# VS_Project_HW01.net
KiCad netlist of a schematic drawn in EasyEDA Pro
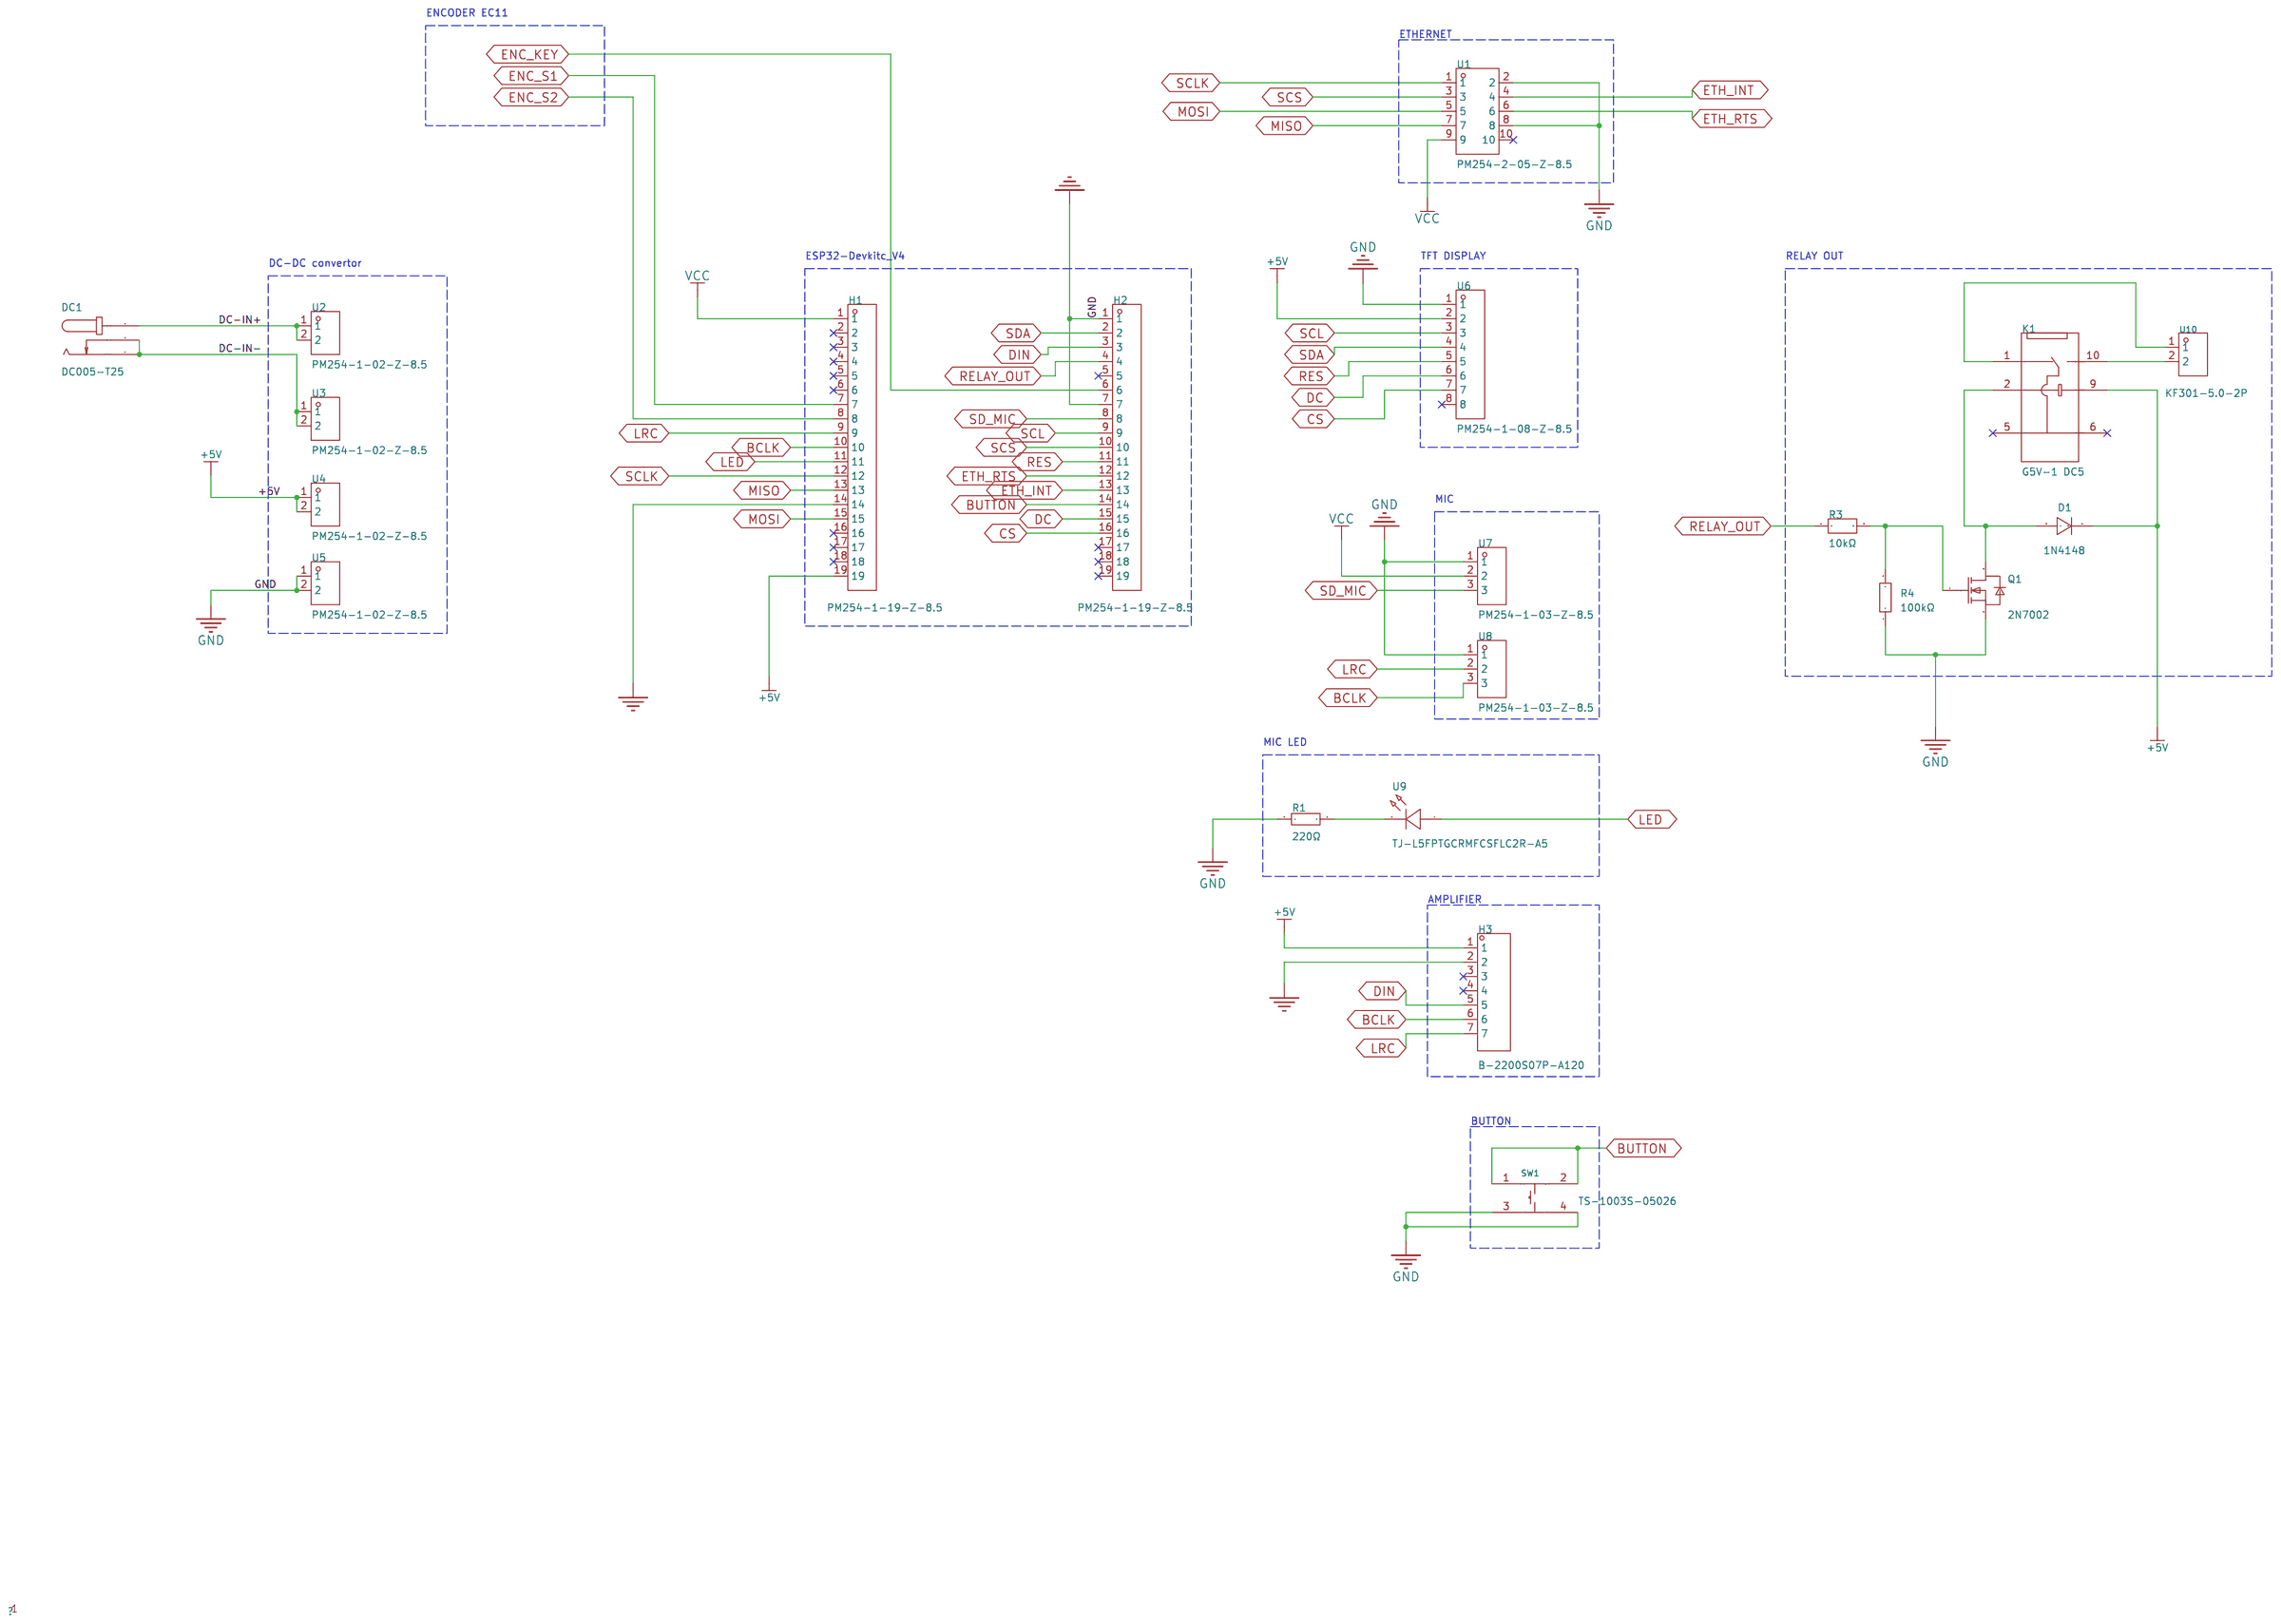
[diagram p0: schematic sheet]

(export (version "E")
  (design (tool "Eeschema 10.0.6"))
  (components
    (comp (ref "D1")
      (value "1N4148")
      (footprint "easyedapro:DO-35_BD2.0-L4.2-P8.20-D0.5-RD")
      (fields (field (name "Manufacturer") "GOOD-ARK(固锝)"))
      (libsource (lib "easyedapro") (part "1N4148_C406389"))
    )
    (comp (ref "DC1")
      (value "DC005-T25")
      (footprint "easyedapro:DC-IN-TH_DC-005-20A-1")
      (fields (field (name "Manufacturer") "SOFNG(硕方)"))
      (libsource (lib "easyedapro") (part "DC005-2.5MM"))
    )
    (comp (ref "H1")
      (value "PM254-1-19-Z-8.5")
      (footprint "easyedapro:HDR-TH_19P-P2.54-V-F")
      (fields (field (name "Manufacturer") "HCTL(华灿天禄)"))
      (libsource (lib "easyedapro") (part "HDR-F_2.54_1x19P"))
    )
    (comp (ref "H2")
      (value "PM254-1-19-Z-8.5")
      (footprint "easyedapro:HDR-TH_19P-P2.54-V-F")
      (fields (field (name "Manufacturer") "HCTL(华灿天禄)"))
      (libsource (lib "easyedapro") (part "HDR-F_2.54_1x19P"))
    )
    (comp (ref "H3")
      (value "B-2200S07P-A120")
      (footprint "easyedapro:HDR-TH_7P-P2.54-V-F")
      (fields (field (name "Manufacturer") "Ckmtw(灿科盟)"))
      (libsource (lib "easyedapro") (part "220S-1*7P H=8.5MM Ytype Gold-plated"))
    )
    (comp (ref "K1")
      (value "G5V-1 DC5")
      (footprint "easyedapro:RELAY-TH_G5V-1")
      (fields (field (name "Manufacturer") "OMRON(欧姆龙)"))
      (libsource (lib "easyedapro") (part "G5V-1-DC3"))
    )
    (comp (ref "Q1")
      (value "2N7002")
      (footprint "easyedapro:SOT-23-3_L2.9-W1.3-P1.90-LS2.4-BR")
      (fields (field (name "Manufacturer") "YFW(佑风微)"))
      (libsource (lib "easyedapro") (part "2N7002_C42395051"))
    )
    (comp (ref "R1")
      (value "220Ω")
      (footprint "easyedapro:R0603")
      (fields (field (name "Manufacturer Part") "RC0603FR-07220RL") (field (name "Manufacturer") "YAGEO(国巨)"))
      (libsource (lib "easyedapro") (part "Res"))
    )
    (comp (ref "R3")
      (value "10kΩ")
      (footprint "easyedapro:R0603")
      (fields (field (name "Manufacturer Part") "RC0603JR-0710KL") (field (name "Manufacturer") "YAGEO(国巨)"))
      (libsource (lib "easyedapro") (part "SCR0603J10K"))
    )
    (comp (ref "R4")
      (value "100kΩ")
      (footprint "easyedapro:R0603")
      (fields (field (name "Manufacturer Part") "RC0603FR-07100KL") (field (name "Manufacturer") "YAGEO(国巨)"))
      (libsource (lib "easyedapro") (part "Res"))
    )
    (comp (ref "SW1")
      (value "TS-1003S-05026")
      (footprint "easyedapro:KEY-SMD_4P-L12.0-W12.0-P5.00-LS15.2")
      (fields (field (name "Manufacturer") "XUNPU(讯普)"))
      (libsource (lib "easyedapro") (part "TS-1003S-05026"))
    )
    (comp (ref "U1")
      (value "PM254-2-05-Z-8.5")
      (footprint "easyedapro:HDR-TH_10P-P2.54-V-F-R2-C5-S2.54")
      (fields (field (name "Manufacturer") "HCTL(华灿天禄)"))
      (libsource (lib "easyedapro") (part "PM254-2-05-Z-8.5"))
    )
    (comp (ref "U2")
      (value "PM254-1-02-Z-8.5")
      (footprint "easyedapro:HDR-TH_2P-P2.54-V-F-3")
      (fields (field (name "Manufacturer") "HCTL(华灿天禄)"))
      (libsource (lib "easyedapro") (part "PM254-1-02-Z-8.5_C3012024"))
    )
    (comp (ref "U3")
      (value "PM254-1-02-Z-8.5")
      (footprint "easyedapro:HDR-TH_2P-P2.54-V-F-3")
      (fields (field (name "Manufacturer") "HCTL(华灿天禄)"))
      (libsource (lib "easyedapro") (part "PM254-1-02-Z-8.5_C3012024"))
    )
    (comp (ref "U4")
      (value "PM254-1-02-Z-8.5")
      (footprint "easyedapro:HDR-TH_2P-P2.54-V-F-3")
      (fields (field (name "Manufacturer") "HCTL(华灿天禄)"))
      (libsource (lib "easyedapro") (part "PM254-1-02-Z-8.5_C3012024"))
    )
    (comp (ref "U5")
      (value "PM254-1-02-Z-8.5")
      (footprint "easyedapro:HDR-TH_2P-P2.54-V-F-3")
      (fields (field (name "Manufacturer") "HCTL(华灿天禄)"))
      (libsource (lib "easyedapro") (part "PM254-1-02-Z-8.5_C3012024"))
    )
    (comp (ref "U6")
      (value "PM254-1-08-Z-8.5")
      (footprint "easyedapro:HDR-TH_8P-P2.54-V-F")
      (fields (field (name "Manufacturer") "HCTL(华灿天禄)"))
      (libsource (lib "easyedapro") (part "PM254-1-08-Z-8.5"))
    )
    (comp (ref "U7")
      (value "PM254-1-03-Z-8.5")
      (footprint "easyedapro:HDR-TH_3P-P2.54-V-F")
      (fields (field (name "Manufacturer") "HCTL(华灿天禄)"))
      (libsource (lib "easyedapro") (part "PM254-1-03-Z-8.5"))
    )
    (comp (ref "U8")
      (value "PM254-1-03-Z-8.5")
      (footprint "easyedapro:HDR-TH_3P-P2.54-V-F")
      (fields (field (name "Manufacturer") "HCTL(华灿天禄)"))
      (libsource (lib "easyedapro") (part "PM254-1-03-Z-8.5"))
    )
    (comp (ref "U9")
      (value "TJ-L5FPTGCRMFCSFLC2R-A5")
      (footprint "easyedapro:LED-TH_BD5.8-P2.54-FD")
      (description "Lamp Holder Type:5mm圆柱形灯头 Emitted Color:Red Lens Color:雾状红透镜")
      (fields (field (name "Manufacturer") "TOGIALED(统佳)"))
      (libsource (lib "easyedapro") (part "TJ-L5FPTGCRMFCSFLC2R-A5"))
    )
    (comp (ref "U10")
      (value "KF301-5.0-2P")
      (footprint "easyedapro:CONN-TH_P5.00_KF301-5.0-2P")
      (fields (field (name "Manufacturer") "KEFA(科发)"))
      (libsource (lib "easyedapro") (part "KF301-5.0-2P"))
    )
  )
  (nets
    (net (code "1") (name "+5V") (class "Default")
      (node (ref "D1") (pin "1") (pinfunction "C_1") (pintype "unspecified"))
      (node (ref "H1") (pin "19") (pinfunction "19_19") (pintype "input"))
      (node (ref "H3") (pin "1") (pinfunction "1_1") (pintype "unspecified"))
      (node (ref "K1") (pin "9") (pinfunction "9_9") (pintype "input"))
      (node (ref "U4") (pin "1") (pinfunction "1_1") (pintype "unspecified"))
      (node (ref "U4") (pin "2") (pinfunction "2_2") (pintype "unspecified"))
      (node (ref "U6") (pin "2") (pinfunction "2_2") (pintype "unspecified"))
    )
    (net (code "2") (name "/DC-IN+") (class "Default")
      (node (ref "DC1") (pin "1") (pinfunction "1_1") (pintype "unspecified"))
      (node (ref "U2") (pin "1") (pinfunction "1_1") (pintype "unspecified"))
      (node (ref "U2") (pin "2") (pinfunction "2_2") (pintype "unspecified"))
    )
    (net (code "3") (name "/DC-IN-") (class "Default")
      (node (ref "DC1") (pin "2") (pinfunction "2_2") (pintype "unspecified"))
      (node (ref "DC1") (pin "3") (pinfunction "3_3") (pintype "unspecified"))
      (node (ref "U3") (pin "1") (pinfunction "1_1") (pintype "unspecified"))
      (node (ref "U3") (pin "2") (pinfunction "2_2") (pintype "unspecified"))
    )
    (net (code "4") (name "BCLK") (class "Default")
      (node (ref "H1") (pin "10") (pinfunction "10_10") (pintype "input"))
      (node (ref "H3") (pin "6") (pinfunction "6_6") (pintype "unspecified"))
      (node (ref "U8") (pin "3") (pinfunction "3_3") (pintype "unspecified"))
    )
    (net (code "5") (name "BUTTON") (class "Default")
      (node (ref "H2") (pin "14") (pinfunction "14_14") (pintype "input"))
      (node (ref "SW1") (pin "1") (pinfunction "1_1") (pintype "input"))
      (node (ref "SW1") (pin "2") (pinfunction "2_2") (pintype "input"))
    )
    (net (code "6") (name "CS") (class "Default")
      (node (ref "H2") (pin "16") (pinfunction "16_16") (pintype "input"))
      (node (ref "U6") (pin "7") (pinfunction "7_7") (pintype "unspecified"))
    )
    (net (code "7") (name "DC") (class "Default")
      (node (ref "H2") (pin "15") (pinfunction "15_15") (pintype "input"))
      (node (ref "U6") (pin "6") (pinfunction "6_6") (pintype "unspecified"))
    )
    (net (code "8") (name "DIN") (class "Default")
      (node (ref "H2") (pin "3") (pinfunction "3_3") (pintype "input"))
      (node (ref "H3") (pin "5") (pinfunction "5_5") (pintype "unspecified"))
    )
    (net (code "9") (name "ENC_KEY") (class "Default")
      (node (ref "H2") (pin "6") (pinfunction "6_6") (pintype "input"))
    )
    (net (code "10") (name "ENC_S1") (class "Default")
      (node (ref "H1") (pin "7") (pinfunction "7_7") (pintype "input"))
    )
    (net (code "11") (name "ENC_S2") (class "Default")
      (node (ref "H1") (pin "8") (pinfunction "8_8") (pintype "input"))
    )
    (net (code "12") (name "ETH_INT") (class "Default")
      (node (ref "H2") (pin "13") (pinfunction "13_13") (pintype "input"))
      (node (ref "U1") (pin "4") (pinfunction "4_4") (pintype "unspecified"))
    )
    (net (code "13") (name "ETH_RTS") (class "Default")
      (node (ref "H2") (pin "12") (pinfunction "12_12") (pintype "input"))
      (node (ref "U1") (pin "6") (pinfunction "6_6") (pintype "unspecified"))
    )
    (net (code "14") (name "GND") (class "Default")
      (node (ref "H1") (pin "14") (pinfunction "14_14") (pintype "input"))
      (node (ref "H2") (pin "1") (pinfunction "1_1") (pintype "input"))
      (node (ref "H2") (pin "7") (pinfunction "7_7") (pintype "input"))
      (node (ref "H3") (pin "2") (pinfunction "2_2") (pintype "unspecified"))
      (node (ref "Q1") (pin "2") (pinfunction "S_2") (pintype "unspecified"))
      (node (ref "R1") (pin "1") (pinfunction "1_1") (pintype "input"))
      (node (ref "R4") (pin "1") (pinfunction "1_1") (pintype "input"))
      (node (ref "SW1") (pin "3") (pinfunction "3_3") (pintype "input"))
      (node (ref "SW1") (pin "4") (pinfunction "4_4") (pintype "input"))
      (node (ref "U1") (pin "2") (pinfunction "2_2") (pintype "unspecified"))
      (node (ref "U1") (pin "8") (pinfunction "8_8") (pintype "unspecified"))
      (node (ref "U5") (pin "1") (pinfunction "1_1") (pintype "unspecified"))
      (node (ref "U5") (pin "2") (pinfunction "2_2") (pintype "unspecified"))
      (node (ref "U6") (pin "1") (pinfunction "1_1") (pintype "unspecified"))
      (node (ref "U7") (pin "1") (pinfunction "1_1") (pintype "unspecified"))
      (node (ref "U8") (pin "1") (pinfunction "1_1") (pintype "unspecified"))
    )
    (net (code "15") (name "LED") (class "Default")
      (node (ref "H1") (pin "11") (pinfunction "11_11") (pintype "input"))
      (node (ref "U9") (pin "1") (pinfunction "A_1") (pintype "unspecified"))
    )
    (net (code "16") (name "LRC") (class "Default")
      (node (ref "H1") (pin "9") (pinfunction "9_9") (pintype "input"))
      (node (ref "H3") (pin "7") (pinfunction "7_7") (pintype "unspecified"))
      (node (ref "U8") (pin "2") (pinfunction "2_2") (pintype "unspecified"))
    )
    (net (code "17") (name "MISO") (class "Default")
      (node (ref "H1") (pin "13") (pinfunction "13_13") (pintype "input"))
      (node (ref "U1") (pin "7") (pinfunction "7_7") (pintype "unspecified"))
    )
    (net (code "18") (name "MOSI") (class "Default")
      (node (ref "H1") (pin "15") (pinfunction "15_15") (pintype "input"))
      (node (ref "U1") (pin "5") (pinfunction "5_5") (pintype "unspecified"))
    )
    (net (code "19") (name "Net-(D1-A)") (class "Default")
      (node (ref "D1") (pin "2") (pinfunction "A_2") (pintype "unspecified"))
      (node (ref "K1") (pin "2") (pinfunction "2_2") (pintype "input"))
      (node (ref "Q1") (pin "3") (pinfunction "D_3") (pintype "unspecified"))
    )
    (net (code "20") (name "Net-(K1-Pad1)") (class "Default")
      (node (ref "K1") (pin "1") (pinfunction "1_1") (pintype "input"))
      (node (ref "U10") (pin "1") (pinfunction "1_1") (pintype "input"))
    )
    (net (code "21") (name "Net-(K1-Pad10)") (class "Default")
      (node (ref "K1") (pin "10") (pinfunction "10_10") (pintype "input"))
      (node (ref "U10") (pin "2") (pinfunction "2_2") (pintype "input"))
    )
    (net (code "22") (name "Net-(Q1-G)") (class "Default")
      (node (ref "Q1") (pin "1") (pinfunction "G_1") (pintype "unspecified"))
      (node (ref "R3") (pin "2") (pinfunction "2_2") (pintype "unspecified"))
      (node (ref "R4") (pin "2") (pinfunction "2_2") (pintype "input"))
    )
    (net (code "23") (name "Net-(U9-K)") (class "Default")
      (node (ref "R1") (pin "2") (pinfunction "2_2") (pintype "input"))
      (node (ref "U9") (pin "2") (pinfunction "K_2") (pintype "unspecified"))
    )
    (net (code "24") (name "RELAY_OUT") (class "Default")
      (node (ref "H2") (pin "4") (pinfunction "4_4") (pintype "input"))
      (node (ref "R3") (pin "1") (pinfunction "1_1") (pintype "unspecified"))
    )
    (net (code "25") (name "RES") (class "Default")
      (node (ref "H2") (pin "11") (pinfunction "11_11") (pintype "input"))
      (node (ref "U6") (pin "5") (pinfunction "5_5") (pintype "unspecified"))
    )
    (net (code "26") (name "SCL") (class "Default")
      (node (ref "H2") (pin "9") (pinfunction "9_9") (pintype "input"))
      (node (ref "U6") (pin "3") (pinfunction "3_3") (pintype "unspecified"))
    )
    (net (code "27") (name "SCLK") (class "Default")
      (node (ref "H1") (pin "12") (pinfunction "12_12") (pintype "input"))
      (node (ref "U1") (pin "1") (pinfunction "1_1") (pintype "unspecified"))
    )
    (net (code "28") (name "SCS") (class "Default")
      (node (ref "H2") (pin "10") (pinfunction "10_10") (pintype "input"))
      (node (ref "U1") (pin "3") (pinfunction "3_3") (pintype "unspecified"))
    )
    (net (code "29") (name "SDA") (class "Default")
      (node (ref "H2") (pin "2") (pinfunction "2_2") (pintype "input"))
      (node (ref "U6") (pin "4") (pinfunction "4_4") (pintype "unspecified"))
    )
    (net (code "30") (name "SD_MIC") (class "Default")
      (node (ref "H2") (pin "8") (pinfunction "8_8") (pintype "input"))
      (node (ref "U7") (pin "3") (pinfunction "3_3") (pintype "unspecified"))
    )
    (net (code "31") (name "VCC") (class "Default")
      (node (ref "H1") (pin "1") (pinfunction "1_1") (pintype "input"))
      (node (ref "U1") (pin "9") (pinfunction "9_9") (pintype "unspecified"))
      (node (ref "U7") (pin "2") (pinfunction "2_2") (pintype "unspecified"))
    )
    (net (code "32") (name "unconnected-(H1-Pad2)") (class "Default")
      (node (ref "H1") (pin "2") (pinfunction "2_2") (pintype "input+no_connect"))
    )
    (net (code "33") (name "unconnected-(H1-Pad3)") (class "Default")
      (node (ref "H1") (pin "3") (pinfunction "3_3") (pintype "input+no_connect"))
    )
    (net (code "34") (name "unconnected-(H1-Pad4)") (class "Default")
      (node (ref "H1") (pin "4") (pinfunction "4_4") (pintype "input+no_connect"))
    )
    (net (code "35") (name "unconnected-(H1-Pad5)") (class "Default")
      (node (ref "H1") (pin "5") (pinfunction "5_5") (pintype "input+no_connect"))
    )
    (net (code "36") (name "unconnected-(H1-Pad6)") (class "Default")
      (node (ref "H1") (pin "6") (pinfunction "6_6") (pintype "input+no_connect"))
    )
    (net (code "37") (name "unconnected-(H1-Pad16)") (class "Default")
      (node (ref "H1") (pin "16") (pinfunction "16_16") (pintype "input+no_connect"))
    )
    (net (code "38") (name "unconnected-(H1-Pad17)") (class "Default")
      (node (ref "H1") (pin "17") (pinfunction "17_17") (pintype "input+no_connect"))
    )
    (net (code "39") (name "unconnected-(H1-Pad18)") (class "Default")
      (node (ref "H1") (pin "18") (pinfunction "18_18") (pintype "input+no_connect"))
    )
    (net (code "40") (name "unconnected-(H2-Pad5)") (class "Default")
      (node (ref "H2") (pin "5") (pinfunction "5_5") (pintype "input+no_connect"))
    )
    (net (code "41") (name "unconnected-(H2-Pad17)") (class "Default")
      (node (ref "H2") (pin "17") (pinfunction "17_17") (pintype "input+no_connect"))
    )
    (net (code "42") (name "unconnected-(H2-Pad18)") (class "Default")
      (node (ref "H2") (pin "18") (pinfunction "18_18") (pintype "input+no_connect"))
    )
    (net (code "43") (name "unconnected-(H2-Pad19)") (class "Default")
      (node (ref "H2") (pin "19") (pinfunction "19_19") (pintype "input+no_connect"))
    )
    (net (code "44") (name "unconnected-(H3-Pad3)") (class "Default")
      (node (ref "H3") (pin "3") (pinfunction "3_3") (pintype "unspecified+no_connect"))
    )
    (net (code "45") (name "unconnected-(H3-Pad4)") (class "Default")
      (node (ref "H3") (pin "4") (pinfunction "4_4") (pintype "unspecified+no_connect"))
    )
    (net (code "46") (name "unconnected-(K1-Pad5)") (class "Default")
      (node (ref "K1") (pin "5") (pinfunction "5_5") (pintype "input+no_connect"))
    )
    (net (code "47") (name "unconnected-(K1-Pad6)") (class "Default")
      (node (ref "K1") (pin "6") (pinfunction "6_6") (pintype "input+no_connect"))
    )
    (net (code "48") (name "unconnected-(U1-Pad10)") (class "Default")
      (node (ref "U1") (pin "10") (pinfunction "10_10") (pintype "unspecified+no_connect"))
    )
    (net (code "49") (name "unconnected-(U6-Pad8)") (class "Default")
      (node (ref "U6") (pin "8") (pinfunction "8_8") (pintype "unspecified+no_connect"))
    )
  )
)
